# L506_M_V1_0.net
KiCad netlist of a schematic drawn in Altium Designer
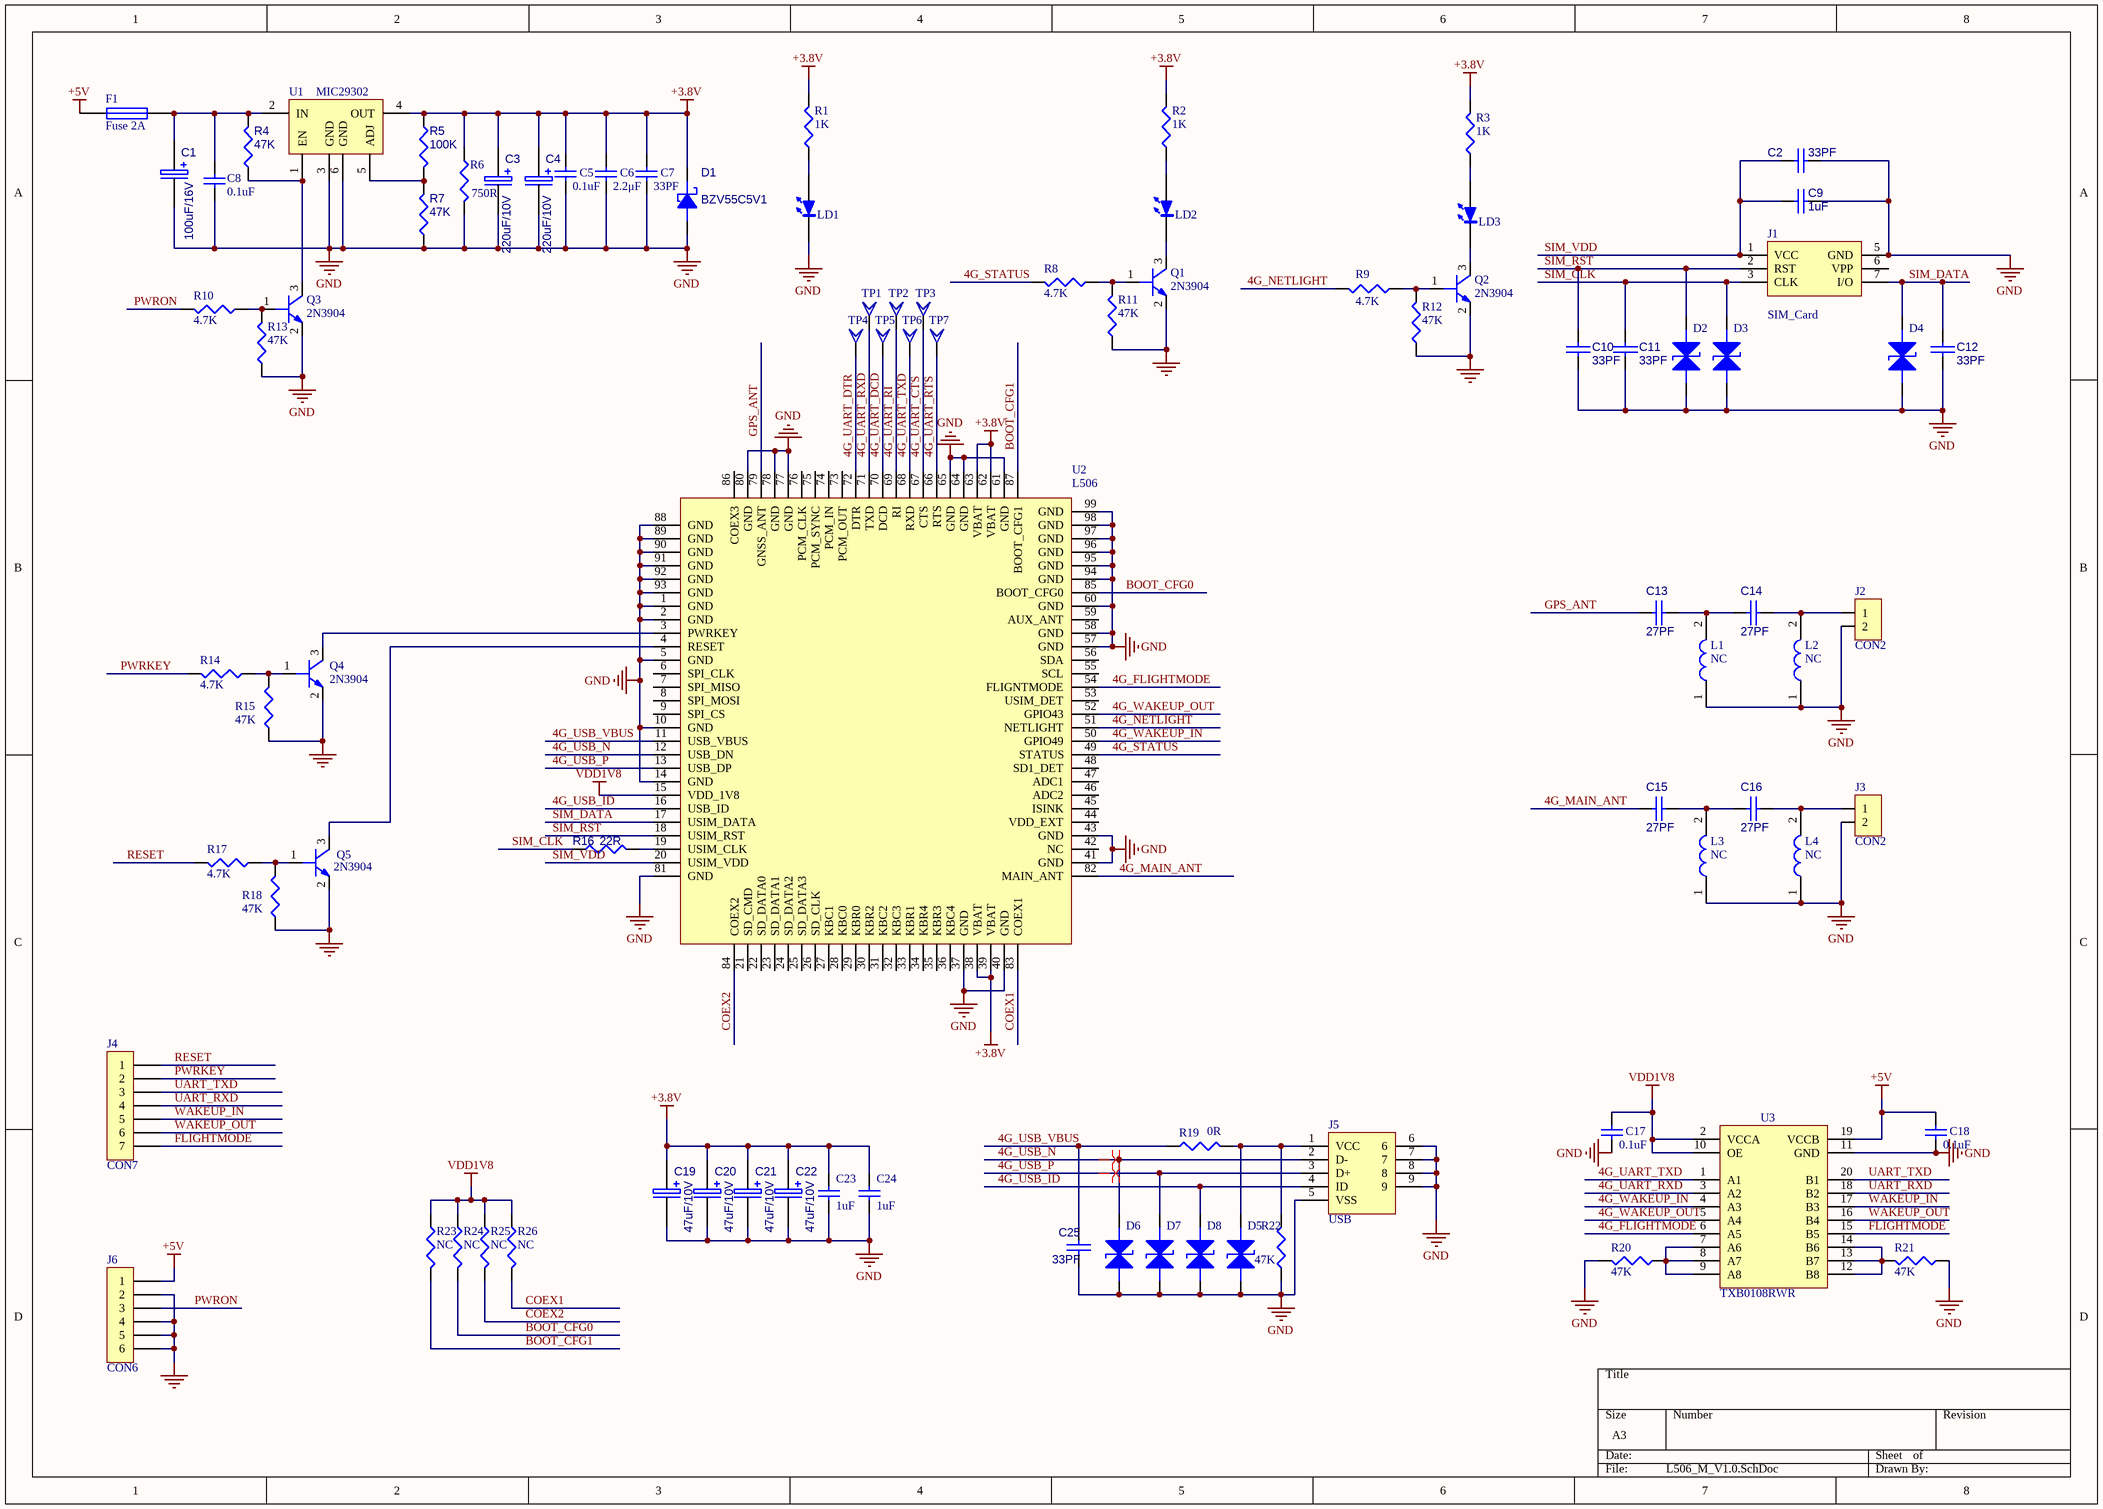
[diagram p0: L506_M_V1.0.SchDoc]

(export (version "E")
  (design (tool "Eeschema 10.0.6"))
  (components
    (comp (ref "C1")
      (value "100uF/16V")
      (footprint "C_TAN_C")
      (description "E-CAP")
      (libsource (lib "*") (part "ECAP"))
    )
    (comp (ref "C2")
      (value "33PF")
      (footprint "0603_C")
      (description "CAP")
      (libsource (lib "") (part "CAP_1"))
    )
    (comp (ref "C3")
      (value "220uF/10V")
      (footprint "C_TAN_D")
      (description "E-CAP")
      (libsource (lib "*") (part "ECAP"))
    )
    (comp (ref "C4")
      (value "220uF/10V")
      (footprint "C_TAN_D")
      (description "E-CAP")
      (libsource (lib "*") (part "ECAP"))
    )
    (comp (ref "C5")
      (value "0.1uF")
      (footprint "0603_C")
      (description "Capacitor")
      (fields (field (name "PUBLISHER") "Altium Limited"))
      (libsource (lib "EP_MCB_V3.00") (part "Cap Semi"))
    )
    (comp (ref "C6")
      (value "2.2μF")
      (footprint "0603_C")
      (description "Capacitor")
      (fields (field (name "PUBLISHER") "Altium Limited"))
      (libsource (lib "EP_MCB_V3.00") (part "Cap Semi"))
    )
    (comp (ref "C7")
      (value "33PF")
      (footprint "0603_C")
      (description "Capacitor")
      (fields (field (name "PUBLISHER") "Altium Limited"))
      (libsource (lib "EP_MCB_V3.00") (part "Cap Semi"))
    )
    (comp (ref "C8")
      (value "0.1uF")
      (footprint "0603_C")
      (description "Capacitor")
      (fields (field (name "PUBLISHER") "Altium Limited"))
      (libsource (lib "EP_MCB_V3.00") (part "Cap Semi"))
    )
    (comp (ref "C9")
      (value "1uF")
      (footprint "0603_C")
      (description "CAP")
      (libsource (lib "") (part "CAP_1"))
    )
    (comp (ref "C10")
      (value "33PF")
      (footprint "0603_C")
      (description "CAP")
      (libsource (lib "*") (part "CAP"))
    )
    (comp (ref "C11")
      (value "33PF")
      (footprint "0603_C")
      (description "CAP")
      (libsource (lib "*") (part "CAP"))
    )
    (comp (ref "C12")
      (value "33PF")
      (footprint "0603_C")
      (description "CAP")
      (libsource (lib "*") (part "CAP"))
    )
    (comp (ref "C13")
      (value "27PF")
      (footprint "0603_C")
      (description "CAP")
      (libsource (lib "") (part "CAP_1"))
    )
    (comp (ref "C14")
      (value "27PF")
      (footprint "0603_C")
      (description "CAP")
      (libsource (lib "") (part "CAP_1"))
    )
    (comp (ref "C15")
      (value "27PF")
      (footprint "0603_C")
      (description "CAP")
      (libsource (lib "") (part "CAP_1"))
    )
    (comp (ref "C16")
      (value "27PF")
      (footprint "0603_C")
      (description "CAP")
      (libsource (lib "") (part "CAP_1"))
    )
    (comp (ref "C17")
      (value "0.1uF")
      (footprint "0603_C")
      (description "Capacitor")
      (fields (field (name "PUBLISHER") "Altium Limited"))
      (libsource (lib "EP_MCB_V3.00") (part "Cap Semi"))
    )
    (comp (ref "C18")
      (value "0.1uF")
      (footprint "0603_C")
      (description "Capacitor")
      (fields (field (name "PUBLISHER") "Altium Limited"))
      (libsource (lib "EP_MCB_V3.00") (part "Cap Semi"))
    )
    (comp (ref "C19")
      (value "47uF/10V")
      (footprint "C_TAN_B")
      (description "E-CAP")
      (libsource (lib "*") (part "ECAP"))
    )
    (comp (ref "C20")
      (value "47uF/10V")
      (footprint "C_TAN_B")
      (description "E-CAP")
      (libsource (lib "*") (part "ECAP"))
    )
    (comp (ref "C21")
      (value "47uF/10V")
      (footprint "C_TAN_B")
      (description "E-CAP")
      (libsource (lib "*") (part "ECAP"))
    )
    (comp (ref "C22")
      (value "47uF/10V")
      (footprint "C_TAN_B")
      (description "E-CAP")
      (libsource (lib "*") (part "ECAP"))
    )
    (comp (ref "C23")
      (value "1uF")
      (footprint "0603_C")
      (description "Capacitor")
      (fields (field (name "PUBLISHER") "Altium Limited"))
      (libsource (lib "EP_MCB_V3.00") (part "Cap Semi"))
    )
    (comp (ref "C24")
      (value "1uF")
      (footprint "0603_C")
      (description "Capacitor")
      (fields (field (name "PUBLISHER") "Altium Limited"))
      (libsource (lib "EP_MCB_V3.00") (part "Cap Semi"))
    )
    (comp (ref "C25")
      (value "33PF")
      (footprint "0603_C")
      (description "CAP")
      (libsource (lib "*") (part "CAP"))
    )
    (comp (ref "D1")
      (value "BZV55C5V1")
      (footprint "SOD-80")
      (libsource (lib "EP_MCB_V4.1") (part "DIODE SCHOTTKY"))
    )
    (comp (ref "D2")
      (value "EGA10603V05A1-B")
      (footprint "0603_R")
      (libsource (lib "MySchlib") (part "DIODE TVS BI-DIR"))
    )
    (comp (ref "D3")
      (value "EGA10603V05A1-B")
      (footprint "0603_R")
      (libsource (lib "MySchlib") (part "DIODE TVS BI-DIR"))
    )
    (comp (ref "D4")
      (value "EGA10603V05A1-B")
      (footprint "0603_R")
      (libsource (lib "MySchlib") (part "DIODE TVS BI-DIR"))
    )
    (comp (ref "D5")
      (value "EGA10603V05A1-B")
      (footprint "0603_R")
      (libsource (lib "MySchlib") (part "DIODE TVS BI-DIR"))
    )
    (comp (ref "D6")
      (value "EGA10603V05A1-B")
      (footprint "0603_R")
      (libsource (lib "MySchlib") (part "DIODE TVS BI-DIR"))
    )
    (comp (ref "D7")
      (value "EGA10603V05A1-B")
      (footprint "0603_R")
      (libsource (lib "MySchlib") (part "DIODE TVS BI-DIR"))
    )
    (comp (ref "D8")
      (value "EGA10603V05A1-B")
      (footprint "0603_R")
      (libsource (lib "MySchlib") (part "DIODE TVS BI-DIR"))
    )
    (comp (ref "F1")
      (value "Fuse 2A")
      (footprint "1812_F")
      (description "Fuse")
      (fields (field (name "PUBLISHER") "Altium Limited"))
      (libsource (lib "Miscellaneous Devices") (part "Fuse 1"))
    )
    (comp (ref "J1")
      (value "SIM_Card")
      (footprint "MicroSIM-6")
      (libsource (lib "MySchlib") (part "SIM_Card"))
    )
    (comp (ref "J2") (value "CON2") (footprint "RF-Z") (libsource (lib "MySchlib") (part "CON2")))
    (comp (ref "J3") (value "CON2") (footprint "RF-Z") (libsource (lib "MySchlib") (part "CON2")))
    (comp (ref "J4") (value "CON7") (footprint "SIP7") (libsource (lib "MySchlib") (part "CON7")))
    (comp (ref "J5") (value "USB") (footprint "MICROUSB_SMD") (libsource (lib "MySchlib") (part "USB-M")))
    (comp (ref "J6") (value "CON6") (footprint "SIP6") (libsource (lib "MySchlib") (part "CON6")))
    (comp (ref "L1") (value "NC") (footprint "0603_R") (libsource (lib "MySchlib") (part "L")))
    (comp (ref "L2") (value "NC") (footprint "0603_R") (libsource (lib "MySchlib") (part "L")))
    (comp (ref "L3") (value "NC") (footprint "0603_R") (libsource (lib "MySchlib") (part "L")))
    (comp (ref "L4") (value "NC") (footprint "0603_R") (libsource (lib "MySchlib") (part "L")))
    (comp (ref "LD1")
      (value "WHITE")
      (footprint "LED_0603")
      (description "LED")
      (libsource (lib "*") (part "LED"))
    )
    (comp (ref "LD2")
      (value "WHITE")
      (footprint "LED_0603")
      (description "LED")
      (libsource (lib "*") (part "LED"))
    )
    (comp (ref "LD3")
      (value "WHITE")
      (footprint "LED_0603")
      (description "LED")
      (libsource (lib "*") (part "LED"))
    )
    (comp (ref "Q1") (value "2N3904") (footprint "SOT23") (libsource (lib "MySchlib") (part "NPN")))
    (comp (ref "Q2") (value "2N3904") (footprint "SOT23") (libsource (lib "MySchlib") (part "NPN")))
    (comp (ref "Q3") (value "2N3904") (footprint "SOT23") (libsource (lib "MySchlib") (part "NPN")))
    (comp (ref "Q4") (value "2N3904") (footprint "SOT23") (libsource (lib "MySchlib") (part "NPN")))
    (comp (ref "Q5") (value "2N3904") (footprint "SOT23") (libsource (lib "MySchlib") (part "NPN")))
    (comp (ref "R1") (value "1K") (footprint "0603_R") (libsource (lib "MySchlib") (part "RES1")))
    (comp (ref "R2") (value "1K") (footprint "0603_R") (libsource (lib "MySchlib") (part "RES1")))
    (comp (ref "R3") (value "1K") (footprint "0603_R") (libsource (lib "MySchlib") (part "RES1")))
    (comp (ref "R4")
      (value "47K")
      (footprint "0603_R")
      (description "RESISTOR")
      (libsource (lib "*") (part "R0.25W"))
    )
    (comp (ref "R5")
      (value "100K")
      (footprint "0603_R")
      (description "RESISTOR")
      (libsource (lib "*") (part "R0.25W"))
    )
    (comp (ref "R6") (value "750R") (footprint "0603_R") (libsource (lib "") (part "RES1_1")))
    (comp (ref "R7")
      (value "47K")
      (footprint "0603_R")
      (description "RESISTOR")
      (libsource (lib "*") (part "R0.25W"))
    )
    (comp (ref "R8") (value "4.7K") (footprint "0603_R") (libsource (lib "MySchlib") (part "RES1")))
    (comp (ref "R9") (value "4.7K") (footprint "0603_R") (libsource (lib "MySchlib") (part "RES1")))
    (comp (ref "R10") (value "4.7K") (footprint "0603_R") (libsource (lib "MySchlib") (part "RES1")))
    (comp (ref "R11") (value "47K") (footprint "0603_R") (libsource (lib "MySchlib") (part "RES1")))
    (comp (ref "R12") (value "47K") (footprint "0603_R") (libsource (lib "MySchlib") (part "RES1")))
    (comp (ref "R13") (value "47K") (footprint "0603_R") (libsource (lib "MySchlib") (part "RES1")))
    (comp (ref "R14") (value "4.7K") (footprint "0603_R") (libsource (lib "MySchlib") (part "RES1")))
    (comp (ref "R15") (value "47K") (footprint "0603_R") (libsource (lib "MySchlib") (part "RES1")))
    (comp (ref "R16")
      (value "22R")
      (footprint "0603_R")
      (description "RESISTOR")
      (libsource (lib "*") (part "R0.25W"))
    )
    (comp (ref "R17") (value "4.7K") (footprint "0603_R") (libsource (lib "MySchlib") (part "RES1")))
    (comp (ref "R18") (value "47K") (footprint "0603_R") (libsource (lib "MySchlib") (part "RES1")))
    (comp (ref "R19") (value "0R") (footprint "0603_R") (libsource (lib "MySchlib") (part "RES1")))
    (comp (ref "R20") (value "47K") (footprint "0603_R") (libsource (lib "MySchlib") (part "RES1")))
    (comp (ref "R21") (value "47K") (footprint "0603_R") (libsource (lib "MySchlib") (part "RES1")))
    (comp (ref "R22") (value "47K") (footprint "0603_R") (libsource (lib "MySchlib") (part "RES1")))
    (comp (ref "R23") (value "NC") (footprint "0603_R") (libsource (lib "MySchlib") (part "RES1")))
    (comp (ref "R24") (value "NC") (footprint "0603_R") (libsource (lib "MySchlib") (part "RES1")))
    (comp (ref "R25") (value "NC") (footprint "0603_R") (libsource (lib "MySchlib") (part "RES1")))
    (comp (ref "R26") (value "NC") (footprint "0603_R") (libsource (lib "MySchlib") (part "RES1")))
    (comp (ref "TP1")
      (value "Component_1")
      (footprint "TP-40")
      (libsource (lib "MySchlib") (part "Component_1"))
    )
    (comp (ref "TP2")
      (value "Component_1")
      (footprint "TP-40")
      (libsource (lib "MySchlib") (part "Component_1"))
    )
    (comp (ref "TP3")
      (value "Component_1")
      (footprint "TP-40")
      (libsource (lib "MySchlib") (part "Component_1"))
    )
    (comp (ref "TP4")
      (value "Component_1")
      (footprint "TP-40")
      (libsource (lib "MySchlib") (part "Component_1"))
    )
    (comp (ref "TP5")
      (value "Component_1")
      (footprint "TP-40")
      (libsource (lib "MySchlib") (part "Component_1"))
    )
    (comp (ref "TP6")
      (value "Component_1")
      (footprint "TP-40")
      (libsource (lib "MySchlib") (part "Component_1"))
    )
    (comp (ref "TP7")
      (value "Component_1")
      (footprint "TP-40")
      (libsource (lib "MySchlib") (part "Component_1"))
    )
    (comp (ref "U1") (value "MIC29302") (footprint "TO-263-5") (libsource (lib "MySchlib") (part "MIC29302")))
    (comp (ref "U2") (value "L506") (footprint "L506") (libsource (lib "MySchlib") (part "L506")))
    (comp (ref "U3")
      (value "TXB0108RWR")
      (footprint "TSSP20")
      (libsource (lib "MySchlib") (part "TXB0108RGYR"))
    )
  )
  (nets
    (net (code "1") (name "+3.8V") (class "Default")
      (node (ref "C19") (pin "1") (pinfunction "+_1") (pintype "passive"))
      (node (ref "C20") (pin "1") (pinfunction "+_1") (pintype "passive"))
      (node (ref "C21") (pin "1") (pinfunction "+_1") (pintype "passive"))
      (node (ref "C22") (pin "1") (pinfunction "+_1") (pintype "passive"))
      (node (ref "C23") (pin "2") (pinfunction "2_2") (pintype "passive"))
      (node (ref "C24") (pin "2") (pinfunction "2_2") (pintype "passive"))
      (node (ref "C3") (pin "1") (pinfunction "+_1") (pintype "passive"))
      (node (ref "C4") (pin "1") (pinfunction "+_1") (pintype "passive"))
      (node (ref "C5") (pin "2") (pinfunction "2_2") (pintype "passive"))
      (node (ref "C6") (pin "2") (pinfunction "2_2") (pintype "passive"))
      (node (ref "C7") (pin "2") (pinfunction "2_2") (pintype "passive"))
      (node (ref "D1") (pin "2") (pinfunction "CATHODE_2") (pintype "passive"))
      (node (ref "R1") (pin "1") (pinfunction "1_1") (pintype "passive"))
      (node (ref "R2") (pin "1") (pinfunction "1_1") (pintype "passive"))
      (node (ref "R3") (pin "1") (pinfunction "1_1") (pintype "passive"))
      (node (ref "R5") (pin "2") (pinfunction "2_2") (pintype "passive"))
      (node (ref "R6") (pin "2") (pinfunction "2_2") (pintype "passive"))
      (node (ref "U1") (pin "4") (pinfunction "OUT_4") (pintype "passive"))
      (node (ref "U2") (pin "38") (pinfunction "VBAT_38") (pintype "passive"))
      (node (ref "U2") (pin "39") (pinfunction "VBAT_39") (pintype "passive"))
      (node (ref "U2") (pin "62") (pinfunction "VBAT_62") (pintype "passive"))
      (node (ref "U2") (pin "63") (pinfunction "VBAT_63") (pintype "passive"))
    )
    (net (code "2") (name "+5V") (class "Default")
      (node (ref "C18") (pin "2") (pinfunction "2_2") (pintype "passive"))
      (node (ref "F1") (pin "1") (pinfunction "1_1") (pintype "passive"))
      (node (ref "J6") (pin "1") (pinfunction "1_1") (pintype "passive"))
      (node (ref "U3") (pin "19") (pinfunction "VCCB_19") (pintype "passive"))
    )
    (net (code "3") (name "/4G_FLIGHTMODE") (class "Default")
      (node (ref "U2") (pin "54") (pinfunction "FLIGNTMODE_54") (pintype "passive"))
      (node (ref "U3") (pin "6") (pinfunction "A5_6") (pintype "passive"))
    )
    (net (code "4") (name "/4G_MAIN_ANT") (class "Default")
      (node (ref "C15") (pin "1") (pinfunction "1_1") (pintype "passive"))
      (node (ref "U2") (pin "82") (pinfunction "MAIN_ANT_82") (pintype "passive"))
    )
    (net (code "5") (name "/4G_NETLIGHT") (class "Default")
      (node (ref "R9") (pin "1") (pinfunction "1_1") (pintype "passive"))
      (node (ref "U2") (pin "51") (pinfunction "NETLIGHT_51") (pintype "passive"))
    )
    (net (code "6") (name "/4G_STATUS") (class "Default")
      (node (ref "R8") (pin "1") (pinfunction "1_1") (pintype "passive"))
      (node (ref "U2") (pin "49") (pinfunction "STATUS_49") (pintype "passive"))
    )
    (net (code "7") (name "/4G_UART_CTS") (class "Default")
      (node (ref "TP3") (pin "1") (pinfunction "1_1") (pintype "passive"))
      (node (ref "U2") (pin "67") (pinfunction "CTS_67") (pintype "passive"))
    )
    (net (code "8") (name "/4G_UART_DCD") (class "Default")
      (node (ref "TP5") (pin "1") (pinfunction "1_1") (pintype "passive"))
      (node (ref "U2") (pin "70") (pinfunction "DCD_70") (pintype "passive"))
    )
    (net (code "9") (name "/4G_UART_DTR") (class "Default")
      (node (ref "TP4") (pin "1") (pinfunction "1_1") (pintype "passive"))
      (node (ref "U2") (pin "72") (pinfunction "DTR_72") (pintype "passive"))
    )
    (net (code "10") (name "/4G_UART_RI") (class "Default")
      (node (ref "TP2") (pin "1") (pinfunction "1_1") (pintype "passive"))
      (node (ref "U2") (pin "69") (pinfunction "RI_69") (pintype "passive"))
    )
    (net (code "11") (name "/4G_UART_RTS") (class "Default")
      (node (ref "TP7") (pin "1") (pinfunction "1_1") (pintype "passive"))
      (node (ref "U2") (pin "66") (pinfunction "RTS_66") (pintype "passive"))
    )
    (net (code "12") (name "/4G_UART_RXD") (class "Default")
      (node (ref "TP1") (pin "1") (pinfunction "1_1") (pintype "passive"))
      (node (ref "U2") (pin "71") (pinfunction "TXD_71") (pintype "passive"))
      (node (ref "U3") (pin "3") (pinfunction "A2_3") (pintype "passive"))
    )
    (net (code "13") (name "/4G_UART_TXD") (class "Default")
      (node (ref "TP6") (pin "1") (pinfunction "1_1") (pintype "passive"))
      (node (ref "U2") (pin "68") (pinfunction "RXD_68") (pintype "passive"))
      (node (ref "U3") (pin "1") (pinfunction "A1_1") (pintype "passive"))
    )
    (net (code "14") (name "/4G_USB_ID") (class "Default")
      (node (ref "D8") (pin "2") (pinfunction "2_2") (pintype "passive"))
      (node (ref "J5") (pin "4") (pinfunction "ID_4") (pintype "passive"))
      (node (ref "U2") (pin "16") (pinfunction "USB_ID_16") (pintype "passive"))
    )
    (net (code "15") (name "/4G_USB_N") (class "Default")
      (node (ref "D6") (pin "2") (pinfunction "2_2") (pintype "passive"))
      (node (ref "J5") (pin "2") (pinfunction "D-_2") (pintype "passive"))
      (node (ref "U2") (pin "12") (pinfunction "USB_DN_12") (pintype "passive"))
    )
    (net (code "16") (name "/4G_USB_P") (class "Default")
      (node (ref "D7") (pin "2") (pinfunction "2_2") (pintype "passive"))
      (node (ref "J5") (pin "3") (pinfunction "D+_3") (pintype "passive"))
      (node (ref "U2") (pin "13") (pinfunction "USB_DP_13") (pintype "passive"))
    )
    (net (code "17") (name "/4G_USB_VBUS") (class "Default")
      (node (ref "C25") (pin "2") (pinfunction "2_2") (pintype "passive"))
      (node (ref "R19") (pin "1") (pinfunction "1_1") (pintype "passive"))
      (node (ref "U2") (pin "11") (pinfunction "USB_VBUS_11") (pintype "passive"))
    )
    (net (code "18") (name "/4G_WAKEUP_IN") (class "Default")
      (node (ref "U2") (pin "50") (pinfunction "GPIO49_50") (pintype "passive"))
      (node (ref "U3") (pin "4") (pinfunction "A3_4") (pintype "passive"))
    )
    (net (code "19") (name "/4G_WAKEUP_OUT") (class "Default")
      (node (ref "U2") (pin "52") (pinfunction "GPIO43_52") (pintype "passive"))
      (node (ref "U3") (pin "5") (pinfunction "A4_5") (pintype "passive"))
    )
    (net (code "20") (name "/BOOT_CFG0") (class "Default")
      (node (ref "R24") (pin "2") (pinfunction "2_2") (pintype "passive"))
      (node (ref "U2") (pin "85") (pinfunction "BOOT_CFG0_85") (pintype "passive"))
    )
    (net (code "21") (name "/BOOT_CFG1") (class "Default")
      (node (ref "R23") (pin "2") (pinfunction "2_2") (pintype "passive"))
      (node (ref "U2") (pin "87") (pinfunction "BOOT_CFG1_87") (pintype "passive"))
    )
    (net (code "22") (name "/COEX1") (class "Default")
      (node (ref "R26") (pin "2") (pinfunction "2_2") (pintype "passive"))
      (node (ref "U2") (pin "83") (pinfunction "COEX1_83") (pintype "passive"))
    )
    (net (code "23") (name "/COEX2") (class "Default")
      (node (ref "R25") (pin "2") (pinfunction "2_2") (pintype "passive"))
      (node (ref "U2") (pin "84") (pinfunction "COEX2_84") (pintype "passive"))
    )
    (net (code "24") (name "/FLIGHTMODE") (class "Default")
      (node (ref "J4") (pin "7") (pinfunction "7_7") (pintype "passive"))
      (node (ref "U3") (pin "15") (pinfunction "B5_15") (pintype "passive"))
    )
    (net (code "25") (name "/GPS_ANT") (class "Default")
      (node (ref "C13") (pin "1") (pinfunction "1_1") (pintype "passive"))
      (node (ref "U2") (pin "79") (pinfunction "GNSS_ANT_79") (pintype "passive"))
    )
    (net (code "26") (name "/PWRKEY") (class "Default")
      (node (ref "J4") (pin "2") (pinfunction "2_2") (pintype "passive"))
      (node (ref "R14") (pin "1") (pinfunction "1_1") (pintype "passive"))
    )
    (net (code "27") (name "/PWRON") (class "Default")
      (node (ref "J6") (pin "3") (pinfunction "3_3") (pintype "passive"))
      (node (ref "R10") (pin "1") (pinfunction "1_1") (pintype "passive"))
    )
    (net (code "28") (name "/RESET") (class "Default")
      (node (ref "J4") (pin "1") (pinfunction "1_1") (pintype "passive"))
      (node (ref "R17") (pin "1") (pinfunction "1_1") (pintype "passive"))
    )
    (net (code "29") (name "/SIM_CLK") (class "Default")
      (node (ref "C11") (pin "2") (pinfunction "2_2") (pintype "passive"))
      (node (ref "D3") (pin "2") (pinfunction "2_2") (pintype "passive"))
      (node (ref "J1") (pin "3") (pinfunction "CLK_3") (pintype "passive"))
      (node (ref "R16") (pin "1") (pinfunction "1_1") (pintype "passive"))
    )
    (net (code "30") (name "/SIM_DATA") (class "Default")
      (node (ref "C12") (pin "2") (pinfunction "2_2") (pintype "passive"))
      (node (ref "D4") (pin "2") (pinfunction "2_2") (pintype "passive"))
      (node (ref "J1") (pin "7") (pinfunction "I/O_7") (pintype "passive"))
      (node (ref "U2") (pin "17") (pinfunction "USIM_DATA_17") (pintype "passive"))
    )
    (net (code "31") (name "/SIM_RST") (class "Default")
      (node (ref "C10") (pin "2") (pinfunction "2_2") (pintype "passive"))
      (node (ref "D2") (pin "2") (pinfunction "2_2") (pintype "passive"))
      (node (ref "J1") (pin "2") (pinfunction "RST_2") (pintype "passive"))
      (node (ref "U2") (pin "18") (pinfunction "USIM_RST_18") (pintype "passive"))
    )
    (net (code "32") (name "/SIM_VDD") (class "Default")
      (node (ref "C2") (pin "1") (pinfunction "1_1") (pintype "passive"))
      (node (ref "C9") (pin "1") (pinfunction "1_1") (pintype "passive"))
      (node (ref "J1") (pin "1") (pinfunction "VCC_1") (pintype "passive"))
      (node (ref "U2") (pin "20") (pinfunction "USIM_VDD_20") (pintype "passive"))
    )
    (net (code "33") (name "/UART_RXD") (class "Default")
      (node (ref "J4") (pin "4") (pinfunction "4_4") (pintype "passive"))
      (node (ref "U3") (pin "18") (pinfunction "B2_18") (pintype "passive"))
    )
    (net (code "34") (name "/UART_TXD") (class "Default")
      (node (ref "J4") (pin "3") (pinfunction "3_3") (pintype "passive"))
      (node (ref "U3") (pin "20") (pinfunction "B1_20") (pintype "passive"))
    )
    (net (code "35") (name "/WAKEUP_IN") (class "Default")
      (node (ref "J4") (pin "5") (pinfunction "5_5") (pintype "passive"))
      (node (ref "U3") (pin "17") (pinfunction "B3_17") (pintype "passive"))
    )
    (net (code "36") (name "/WAKEUP_OUT") (class "Default")
      (node (ref "J4") (pin "6") (pinfunction "6_6") (pintype "passive"))
      (node (ref "U3") (pin "16") (pinfunction "B4_16") (pintype "passive"))
    )
    (net (code "37") (name "GND") (class "Default")
      (node (ref "C1") (pin "2") (pinfunction "-_2") (pintype "passive"))
      (node (ref "C10") (pin "1") (pinfunction "1_1") (pintype "passive"))
      (node (ref "C11") (pin "1") (pinfunction "1_1") (pintype "passive"))
      (node (ref "C12") (pin "1") (pinfunction "1_1") (pintype "passive"))
      (node (ref "C17") (pin "1") (pinfunction "1_1") (pintype "passive"))
      (node (ref "C18") (pin "1") (pinfunction "1_1") (pintype "passive"))
      (node (ref "C19") (pin "2") (pinfunction "-_2") (pintype "passive"))
      (node (ref "C2") (pin "2") (pinfunction "2_2") (pintype "passive"))
      (node (ref "C20") (pin "2") (pinfunction "-_2") (pintype "passive"))
      (node (ref "C21") (pin "2") (pinfunction "-_2") (pintype "passive"))
      (node (ref "C22") (pin "2") (pinfunction "-_2") (pintype "passive"))
      (node (ref "C23") (pin "1") (pinfunction "1_1") (pintype "passive"))
      (node (ref "C24") (pin "1") (pinfunction "1_1") (pintype "passive"))
      (node (ref "C25") (pin "1") (pinfunction "1_1") (pintype "passive"))
      (node (ref "C3") (pin "2") (pinfunction "-_2") (pintype "passive"))
      (node (ref "C4") (pin "2") (pinfunction "-_2") (pintype "passive"))
      (node (ref "C5") (pin "1") (pinfunction "1_1") (pintype "passive"))
      (node (ref "C6") (pin "1") (pinfunction "1_1") (pintype "passive"))
      (node (ref "C7") (pin "1") (pinfunction "1_1") (pintype "passive"))
      (node (ref "C8") (pin "1") (pinfunction "1_1") (pintype "passive"))
      (node (ref "C9") (pin "2") (pinfunction "2_2") (pintype "passive"))
      (node (ref "D1") (pin "1") (pinfunction "ANODE_1") (pintype "passive"))
      (node (ref "D2") (pin "1") (pinfunction "1_1") (pintype "passive"))
      (node (ref "D3") (pin "1") (pinfunction "1_1") (pintype "passive"))
      (node (ref "D4") (pin "1") (pinfunction "1_1") (pintype "passive"))
      (node (ref "D5") (pin "1") (pinfunction "1_1") (pintype "passive"))
      (node (ref "D6") (pin "1") (pinfunction "1_1") (pintype "passive"))
      (node (ref "D7") (pin "1") (pinfunction "1_1") (pintype "passive"))
      (node (ref "D8") (pin "1") (pinfunction "1_1") (pintype "passive"))
      (node (ref "J1") (pin "5") (pinfunction "GND_5") (pintype "passive"))
      (node (ref "J2") (pin "2") (pinfunction "2_2") (pintype "passive"))
      (node (ref "J3") (pin "2") (pinfunction "2_2") (pintype "passive"))
      (node (ref "J5") (pin "5") (pinfunction "VSS_5") (pintype "passive"))
      (node (ref "J5") (pin "6") (pinfunction "6_6") (pintype "passive"))
      (node (ref "J5") (pin "7") (pinfunction "7_7") (pintype "passive"))
      (node (ref "J5") (pin "8") (pinfunction "8_8") (pintype "passive"))
      (node (ref "J5") (pin "9") (pinfunction "9_9") (pintype "passive"))
      (node (ref "J6") (pin "2") (pinfunction "2_2") (pintype "passive"))
      (node (ref "J6") (pin "4") (pinfunction "4_4") (pintype "passive"))
      (node (ref "J6") (pin "5") (pinfunction "5_5") (pintype "passive"))
      (node (ref "J6") (pin "6") (pinfunction "6_6") (pintype "passive"))
      (node (ref "L1") (pin "1") (pinfunction "1_1") (pintype "passive"))
      (node (ref "L2") (pin "1") (pinfunction "1_1") (pintype "passive"))
      (node (ref "L3") (pin "1") (pinfunction "1_1") (pintype "passive"))
      (node (ref "L4") (pin "1") (pinfunction "1_1") (pintype "passive"))
      (node (ref "LD1") (pin "K") (pinfunction "K_K") (pintype "passive"))
      (node (ref "Q1") (pin "2") (pinfunction "EMITTER_2") (pintype "passive"))
      (node (ref "Q2") (pin "2") (pinfunction "EMITTER_2") (pintype "passive"))
      (node (ref "Q3") (pin "2") (pinfunction "EMITTER_2") (pintype "passive"))
      (node (ref "Q4") (pin "2") (pinfunction "EMITTER_2") (pintype "passive"))
      (node (ref "Q5") (pin "2") (pinfunction "EMITTER_2") (pintype "passive"))
      (node (ref "R11") (pin "2") (pinfunction "2_2") (pintype "passive"))
      (node (ref "R12") (pin "2") (pinfunction "2_2") (pintype "passive"))
      (node (ref "R13") (pin "2") (pinfunction "2_2") (pintype "passive"))
      (node (ref "R15") (pin "2") (pinfunction "2_2") (pintype "passive"))
      (node (ref "R18") (pin "2") (pinfunction "2_2") (pintype "passive"))
      (node (ref "R20") (pin "2") (pinfunction "2_2") (pintype "passive"))
      (node (ref "R21") (pin "1") (pinfunction "1_1") (pintype "passive"))
      (node (ref "R22") (pin "2") (pinfunction "2_2") (pintype "passive"))
      (node (ref "R6") (pin "1") (pinfunction "1_1") (pintype "passive"))
      (node (ref "R7") (pin "2") (pinfunction "2_2") (pintype "passive"))
      (node (ref "U1") (pin "3") (pinfunction "GND_3") (pintype "passive"))
      (node (ref "U1") (pin "6") (pinfunction "GND_6") (pintype "passive"))
      (node (ref "U2") (pin "1") (pinfunction "GND_1") (pintype "passive"))
      (node (ref "U2") (pin "10") (pinfunction "GND_10") (pintype "passive"))
      (node (ref "U2") (pin "14") (pinfunction "GND_14") (pintype "passive"))
      (node (ref "U2") (pin "2") (pinfunction "GND_2") (pintype "passive"))
      (node (ref "U2") (pin "37") (pinfunction "GND_37") (pintype "passive"))
      (node (ref "U2") (pin "40") (pinfunction "GND_40") (pintype "passive"))
      (node (ref "U2") (pin "41") (pinfunction "GND_41") (pintype "passive"))
      (node (ref "U2") (pin "43") (pinfunction "GND_43") (pintype "passive"))
      (node (ref "U2") (pin "5") (pinfunction "GND_5") (pintype "passive"))
      (node (ref "U2") (pin "57") (pinfunction "GND_57") (pintype "passive"))
      (node (ref "U2") (pin "58") (pinfunction "GND_58") (pintype "passive"))
      (node (ref "U2") (pin "60") (pinfunction "GND_60") (pintype "passive"))
      (node (ref "U2") (pin "61") (pinfunction "GND_61") (pintype "passive"))
      (node (ref "U2") (pin "64") (pinfunction "GND_64") (pintype "passive"))
      (node (ref "U2") (pin "65") (pinfunction "GND_65") (pintype "passive"))
      (node (ref "U2") (pin "77") (pinfunction "GND_77") (pintype "passive"))
      (node (ref "U2") (pin "78") (pinfunction "GND_78") (pintype "passive"))
      (node (ref "U2") (pin "80") (pinfunction "GND_80") (pintype "passive"))
      (node (ref "U2") (pin "81") (pinfunction "GND_81") (pintype "passive"))
      (node (ref "U2") (pin "88") (pinfunction "GND_88") (pintype "passive"))
      (node (ref "U2") (pin "89") (pinfunction "GND_89") (pintype "passive"))
      (node (ref "U2") (pin "90") (pinfunction "GND_90") (pintype "passive"))
      (node (ref "U2") (pin "91") (pinfunction "GND_91") (pintype "passive"))
      (node (ref "U2") (pin "92") (pinfunction "GND_92") (pintype "passive"))
      (node (ref "U2") (pin "93") (pinfunction "GND_93") (pintype "passive"))
      (node (ref "U2") (pin "94") (pinfunction "GND_94") (pintype "passive"))
      (node (ref "U2") (pin "95") (pinfunction "GND_95") (pintype "passive"))
      (node (ref "U2") (pin "96") (pinfunction "GND_96") (pintype "passive"))
      (node (ref "U2") (pin "97") (pinfunction "GND_97") (pintype "passive"))
      (node (ref "U2") (pin "98") (pinfunction "GND_98") (pintype "passive"))
      (node (ref "U2") (pin "99") (pinfunction "GND_99") (pintype "passive"))
      (node (ref "U3") (pin "11") (pinfunction "GND_11") (pintype "passive"))
    )
    (net (code "38") (name "Net-(C1-+)") (class "Default")
      (node (ref "C1") (pin "1") (pinfunction "+_1") (pintype "passive"))
      (node (ref "C8") (pin "2") (pinfunction "2_2") (pintype "passive"))
      (node (ref "F1") (pin "2") (pinfunction "2_2") (pintype "passive"))
      (node (ref "R4") (pin "1") (pinfunction "1_1") (pintype "passive"))
      (node (ref "U1") (pin "2") (pinfunction "IN_2") (pintype "passive"))
    )
    (net (code "39") (name "Net-(C13-Pad2)") (class "Default")
      (node (ref "C13") (pin "2") (pinfunction "2_2") (pintype "passive"))
      (node (ref "C14") (pin "1") (pinfunction "1_1") (pintype "passive"))
      (node (ref "L1") (pin "2") (pinfunction "2_2") (pintype "passive"))
    )
    (net (code "40") (name "Net-(C14-Pad2)") (class "Default")
      (node (ref "C14") (pin "2") (pinfunction "2_2") (pintype "passive"))
      (node (ref "J2") (pin "1") (pinfunction "1_1") (pintype "passive"))
      (node (ref "L2") (pin "2") (pinfunction "2_2") (pintype "passive"))
    )
    (net (code "41") (name "Net-(C15-Pad2)") (class "Default")
      (node (ref "C15") (pin "2") (pinfunction "2_2") (pintype "passive"))
      (node (ref "C16") (pin "1") (pinfunction "1_1") (pintype "passive"))
      (node (ref "L3") (pin "2") (pinfunction "2_2") (pintype "passive"))
    )
    (net (code "42") (name "Net-(C16-Pad2)") (class "Default")
      (node (ref "C16") (pin "2") (pinfunction "2_2") (pintype "passive"))
      (node (ref "J3") (pin "1") (pinfunction "1_1") (pintype "passive"))
      (node (ref "L4") (pin "2") (pinfunction "2_2") (pintype "passive"))
    )
    (net (code "43") (name "Net-(J5-VCC)") (class "Default")
      (node (ref "D5") (pin "2") (pinfunction "2_2") (pintype "passive"))
      (node (ref "J5") (pin "1") (pinfunction "VCC_1") (pintype "passive"))
      (node (ref "R19") (pin "2") (pinfunction "2_2") (pintype "passive"))
      (node (ref "R22") (pin "1") (pinfunction "1_1") (pintype "passive"))
    )
    (net (code "44") (name "Net-(LD1-PadA)") (class "Default")
      (node (ref "LD1") (pin "A") (pinfunction "A_A") (pintype "passive"))
      (node (ref "R1") (pin "2") (pinfunction "2_2") (pintype "passive"))
    )
    (net (code "45") (name "Net-(LD2-PadA)") (class "Default")
      (node (ref "LD2") (pin "A") (pinfunction "A_A") (pintype "passive"))
      (node (ref "R2") (pin "2") (pinfunction "2_2") (pintype "passive"))
    )
    (net (code "46") (name "Net-(LD3-PadA)") (class "Default")
      (node (ref "LD3") (pin "A") (pinfunction "A_A") (pintype "passive"))
      (node (ref "R3") (pin "2") (pinfunction "2_2") (pintype "passive"))
    )
    (net (code "47") (name "Net-(Q1-BASE)") (class "Default")
      (node (ref "Q1") (pin "1") (pinfunction "BASE_1") (pintype "passive"))
      (node (ref "R11") (pin "1") (pinfunction "1_1") (pintype "passive"))
      (node (ref "R8") (pin "2") (pinfunction "2_2") (pintype "passive"))
    )
    (net (code "48") (name "Net-(Q1-COLLECTOR)") (class "Default")
      (node (ref "LD2") (pin "K") (pinfunction "K_K") (pintype "passive"))
      (node (ref "Q1") (pin "3") (pinfunction "COLLECTOR_3") (pintype "passive"))
    )
    (net (code "49") (name "Net-(Q2-BASE)") (class "Default")
      (node (ref "Q2") (pin "1") (pinfunction "BASE_1") (pintype "passive"))
      (node (ref "R12") (pin "1") (pinfunction "1_1") (pintype "passive"))
      (node (ref "R9") (pin "2") (pinfunction "2_2") (pintype "passive"))
    )
    (net (code "50") (name "Net-(Q2-COLLECTOR)") (class "Default")
      (node (ref "LD3") (pin "K") (pinfunction "K_K") (pintype "passive"))
      (node (ref "Q2") (pin "3") (pinfunction "COLLECTOR_3") (pintype "passive"))
    )
    (net (code "51") (name "Net-(Q3-BASE)") (class "Default")
      (node (ref "Q3") (pin "1") (pinfunction "BASE_1") (pintype "passive"))
      (node (ref "R10") (pin "2") (pinfunction "2_2") (pintype "passive"))
      (node (ref "R13") (pin "1") (pinfunction "1_1") (pintype "passive"))
    )
    (net (code "52") (name "Net-(Q3-COLLECTOR)") (class "Default")
      (node (ref "Q3") (pin "3") (pinfunction "COLLECTOR_3") (pintype "passive"))
      (node (ref "R4") (pin "2") (pinfunction "2_2") (pintype "passive"))
      (node (ref "U1") (pin "1") (pinfunction "EN_1") (pintype "passive"))
    )
    (net (code "53") (name "Net-(Q4-BASE)") (class "Default")
      (node (ref "Q4") (pin "1") (pinfunction "BASE_1") (pintype "passive"))
      (node (ref "R14") (pin "2") (pinfunction "2_2") (pintype "passive"))
      (node (ref "R15") (pin "1") (pinfunction "1_1") (pintype "passive"))
    )
    (net (code "54") (name "Net-(Q4-COLLECTOR)") (class "Default")
      (node (ref "Q4") (pin "3") (pinfunction "COLLECTOR_3") (pintype "passive"))
      (node (ref "U2") (pin "3") (pinfunction "PWRKEY_3") (pintype "passive"))
    )
    (net (code "55") (name "Net-(Q5-BASE)") (class "Default")
      (node (ref "Q5") (pin "1") (pinfunction "BASE_1") (pintype "passive"))
      (node (ref "R17") (pin "2") (pinfunction "2_2") (pintype "passive"))
      (node (ref "R18") (pin "1") (pinfunction "1_1") (pintype "passive"))
    )
    (net (code "56") (name "Net-(Q5-COLLECTOR)") (class "Default")
      (node (ref "Q5") (pin "3") (pinfunction "COLLECTOR_3") (pintype "passive"))
      (node (ref "U2") (pin "4") (pinfunction "RESET_4") (pintype "passive"))
    )
    (net (code "57") (name "Net-(U1-ADJ)") (class "Default")
      (node (ref "R5") (pin "1") (pinfunction "1_1") (pintype "passive"))
      (node (ref "R7") (pin "1") (pinfunction "1_1") (pintype "passive"))
      (node (ref "U1") (pin "5") (pinfunction "ADJ_5") (pintype "passive"))
    )
    (net (code "58") (name "Net-(U2-USIM_CLK)") (class "Default")
      (node (ref "R16") (pin "2") (pinfunction "2_2") (pintype "passive"))
      (node (ref "U2") (pin "19") (pinfunction "USIM_CLK_19") (pintype "passive"))
    )
    (net (code "59") (name "Net-(U3-A6)") (class "Default")
      (node (ref "R20") (pin "1") (pinfunction "1_1") (pintype "passive"))
      (node (ref "U3") (pin "7") (pinfunction "A6_7") (pintype "passive"))
      (node (ref "U3") (pin "8") (pinfunction "A7_8") (pintype "passive"))
      (node (ref "U3") (pin "9") (pinfunction "A8_9") (pintype "passive"))
    )
    (net (code "60") (name "Net-(U3-B6)") (class "Default")
      (node (ref "R21") (pin "2") (pinfunction "2_2") (pintype "passive"))
      (node (ref "U3") (pin "12") (pinfunction "B8_12") (pintype "passive"))
      (node (ref "U3") (pin "13") (pinfunction "B7_13") (pintype "passive"))
      (node (ref "U3") (pin "14") (pinfunction "B6_14") (pintype "passive"))
    )
    (net (code "61") (name "VDD1V8") (class "Default")
      (node (ref "C17") (pin "2") (pinfunction "2_2") (pintype "passive"))
      (node (ref "R23") (pin "1") (pinfunction "1_1") (pintype "passive"))
      (node (ref "R24") (pin "1") (pinfunction "1_1") (pintype "passive"))
      (node (ref "R25") (pin "1") (pinfunction "1_1") (pintype "passive"))
      (node (ref "R26") (pin "1") (pinfunction "1_1") (pintype "passive"))
      (node (ref "U2") (pin "15") (pinfunction "VDD_1V8_15") (pintype "passive"))
      (node (ref "U3") (pin "10") (pinfunction "OE_10") (pintype "passive"))
      (node (ref "U3") (pin "2") (pinfunction "VCCA_2") (pintype "passive"))
    )
    (net (code "62") (name "unconnected-(J1-VPP-Pad6)") (class "Default")
      (node (ref "J1") (pin "6") (pinfunction "VPP_6") (pintype "passive"))
    )
    (net (code "63") (name "unconnected-(U2-ADC1-Pad47)") (class "Default")
      (node (ref "U2") (pin "47") (pinfunction "ADC1_47") (pintype "passive"))
    )
    (net (code "64") (name "unconnected-(U2-ADC2-Pad46)") (class "Default")
      (node (ref "U2") (pin "46") (pinfunction "ADC2_46") (pintype "passive"))
    )
    (net (code "65") (name "unconnected-(U2-AUX_ANT-Pad59)") (class "Default")
      (node (ref "U2") (pin "59") (pinfunction "AUX_ANT_59") (pintype "passive"))
    )
    (net (code "66") (name "unconnected-(U2-COEX3-Pad86)") (class "Default")
      (node (ref "U2") (pin "86") (pinfunction "COEX3_86") (pintype "passive"))
    )
    (net (code "67") (name "unconnected-(U2-ISINK-Pad45)") (class "Default")
      (node (ref "U2") (pin "45") (pinfunction "ISINK_45") (pintype "passive"))
    )
    (net (code "68") (name "unconnected-(U2-KBC0-Pad28)") (class "Default")
      (node (ref "U2") (pin "28") (pinfunction "KBC0_28") (pintype "passive"))
    )
    (net (code "69") (name "unconnected-(U2-KBC1-Pad27)") (class "Default")
      (node (ref "U2") (pin "27") (pinfunction "KBC1_27") (pintype "passive"))
    )
    (net (code "70") (name "unconnected-(U2-KBC2-Pad31)") (class "Default")
      (node (ref "U2") (pin "31") (pinfunction "KBC2_31") (pintype "passive"))
    )
    (net (code "71") (name "unconnected-(U2-KBC3-Pad32)") (class "Default")
      (node (ref "U2") (pin "32") (pinfunction "KBC3_32") (pintype "passive"))
    )
    (net (code "72") (name "unconnected-(U2-KBC4-Pad36)") (class "Default")
      (node (ref "U2") (pin "36") (pinfunction "KBC4_36") (pintype "passive"))
    )
    (net (code "73") (name "unconnected-(U2-KBR0-Pad29)") (class "Default")
      (node (ref "U2") (pin "29") (pinfunction "KBR0_29") (pintype "passive"))
    )
    (net (code "74") (name "unconnected-(U2-KBR1-Pad33)") (class "Default")
      (node (ref "U2") (pin "33") (pinfunction "KBR1_33") (pintype "passive"))
    )
    (net (code "75") (name "unconnected-(U2-KBR2-Pad30)") (class "Default")
      (node (ref "U2") (pin "30") (pinfunction "KBR2_30") (pintype "passive"))
    )
    (net (code "76") (name "unconnected-(U2-KBR3-Pad35)") (class "Default")
      (node (ref "U2") (pin "35") (pinfunction "KBR3_35") (pintype "passive"))
    )
    (net (code "77") (name "unconnected-(U2-KBR4-Pad34)") (class "Default")
      (node (ref "U2") (pin "34") (pinfunction "KBR4_34") (pintype "passive"))
    )
    (net (code "78") (name "unconnected-(U2-NC-Pad42)") (class "Default")
      (node (ref "U2") (pin "42") (pinfunction "NC_42") (pintype "passive"))
    )
    (net (code "79") (name "unconnected-(U2-PCM_CLK-Pad76)") (class "Default")
      (node (ref "U2") (pin "76") (pinfunction "PCM_CLK_76") (pintype "passive"))
    )
    (net (code "80") (name "unconnected-(U2-PCM_IN-Pad74)") (class "Default")
      (node (ref "U2") (pin "74") (pinfunction "PCM_IN_74") (pintype "passive"))
    )
    (net (code "81") (name "unconnected-(U2-PCM_OUT-Pad73)") (class "Default")
      (node (ref "U2") (pin "73") (pinfunction "PCM_OUT_73") (pintype "passive"))
    )
    (net (code "82") (name "unconnected-(U2-PCM_SYNC-Pad75)") (class "Default")
      (node (ref "U2") (pin "75") (pinfunction "PCM_SYNC_75") (pintype "passive"))
    )
    (net (code "83") (name "unconnected-(U2-SCL-Pad55)") (class "Default")
      (node (ref "U2") (pin "55") (pinfunction "SCL_55") (pintype "passive"))
    )
    (net (code "84") (name "unconnected-(U2-SD1_DET-Pad48)") (class "Default")
      (node (ref "U2") (pin "48") (pinfunction "SD1_DET_48") (pintype "passive"))
    )
    (net (code "85") (name "unconnected-(U2-SDA-Pad56)") (class "Default")
      (node (ref "U2") (pin "56") (pinfunction "SDA_56") (pintype "passive"))
    )
    (net (code "86") (name "unconnected-(U2-SD_CLK-Pad26)") (class "Default")
      (node (ref "U2") (pin "26") (pinfunction "SD_CLK_26") (pintype "passive"))
    )
    (net (code "87") (name "unconnected-(U2-SD_CMD-Pad21)") (class "Default")
      (node (ref "U2") (pin "21") (pinfunction "SD_CMD_21") (pintype "passive"))
    )
    (net (code "88") (name "unconnected-(U2-SD_DATA0-Pad22)") (class "Default")
      (node (ref "U2") (pin "22") (pinfunction "SD_DATA0_22") (pintype "passive"))
    )
    (net (code "89") (name "unconnected-(U2-SD_DATA1-Pad23)") (class "Default")
      (node (ref "U2") (pin "23") (pinfunction "SD_DATA1_23") (pintype "passive"))
    )
    (net (code "90") (name "unconnected-(U2-SD_DATA2-Pad24)") (class "Default")
      (node (ref "U2") (pin "24") (pinfunction "SD_DATA2_24") (pintype "passive"))
    )
    (net (code "91") (name "unconnected-(U2-SD_DATA3-Pad25)") (class "Default")
      (node (ref "U2") (pin "25") (pinfunction "SD_DATA3_25") (pintype "passive"))
    )
    (net (code "92") (name "unconnected-(U2-SPI_CLK-Pad6)") (class "Default")
      (node (ref "U2") (pin "6") (pinfunction "SPI_CLK_6") (pintype "passive"))
    )
    (net (code "93") (name "unconnected-(U2-SPI_CS-Pad9)") (class "Default")
      (node (ref "U2") (pin "9") (pinfunction "SPI_CS_9") (pintype "passive"))
    )
    (net (code "94") (name "unconnected-(U2-SPI_MISO-Pad7)") (class "Default")
      (node (ref "U2") (pin "7") (pinfunction "SPI_MISO_7") (pintype "passive"))
    )
    (net (code "95") (name "unconnected-(U2-SPI_MOSI-Pad8)") (class "Default")
      (node (ref "U2") (pin "8") (pinfunction "SPI_MOSI_8") (pintype "passive"))
    )
    (net (code "96") (name "unconnected-(U2-USIM_DET-Pad53)") (class "Default")
      (node (ref "U2") (pin "53") (pinfunction "USIM_DET_53") (pintype "passive"))
    )
    (net (code "97") (name "unconnected-(U2-VDD_EXT-Pad44)") (class "Default")
      (node (ref "U2") (pin "44") (pinfunction "VDD_EXT_44") (pintype "passive"))
    )
  )
)
